# SoilMoistureSensorv2.net
KiCad netlist of a schematic drawn in Altium Designer
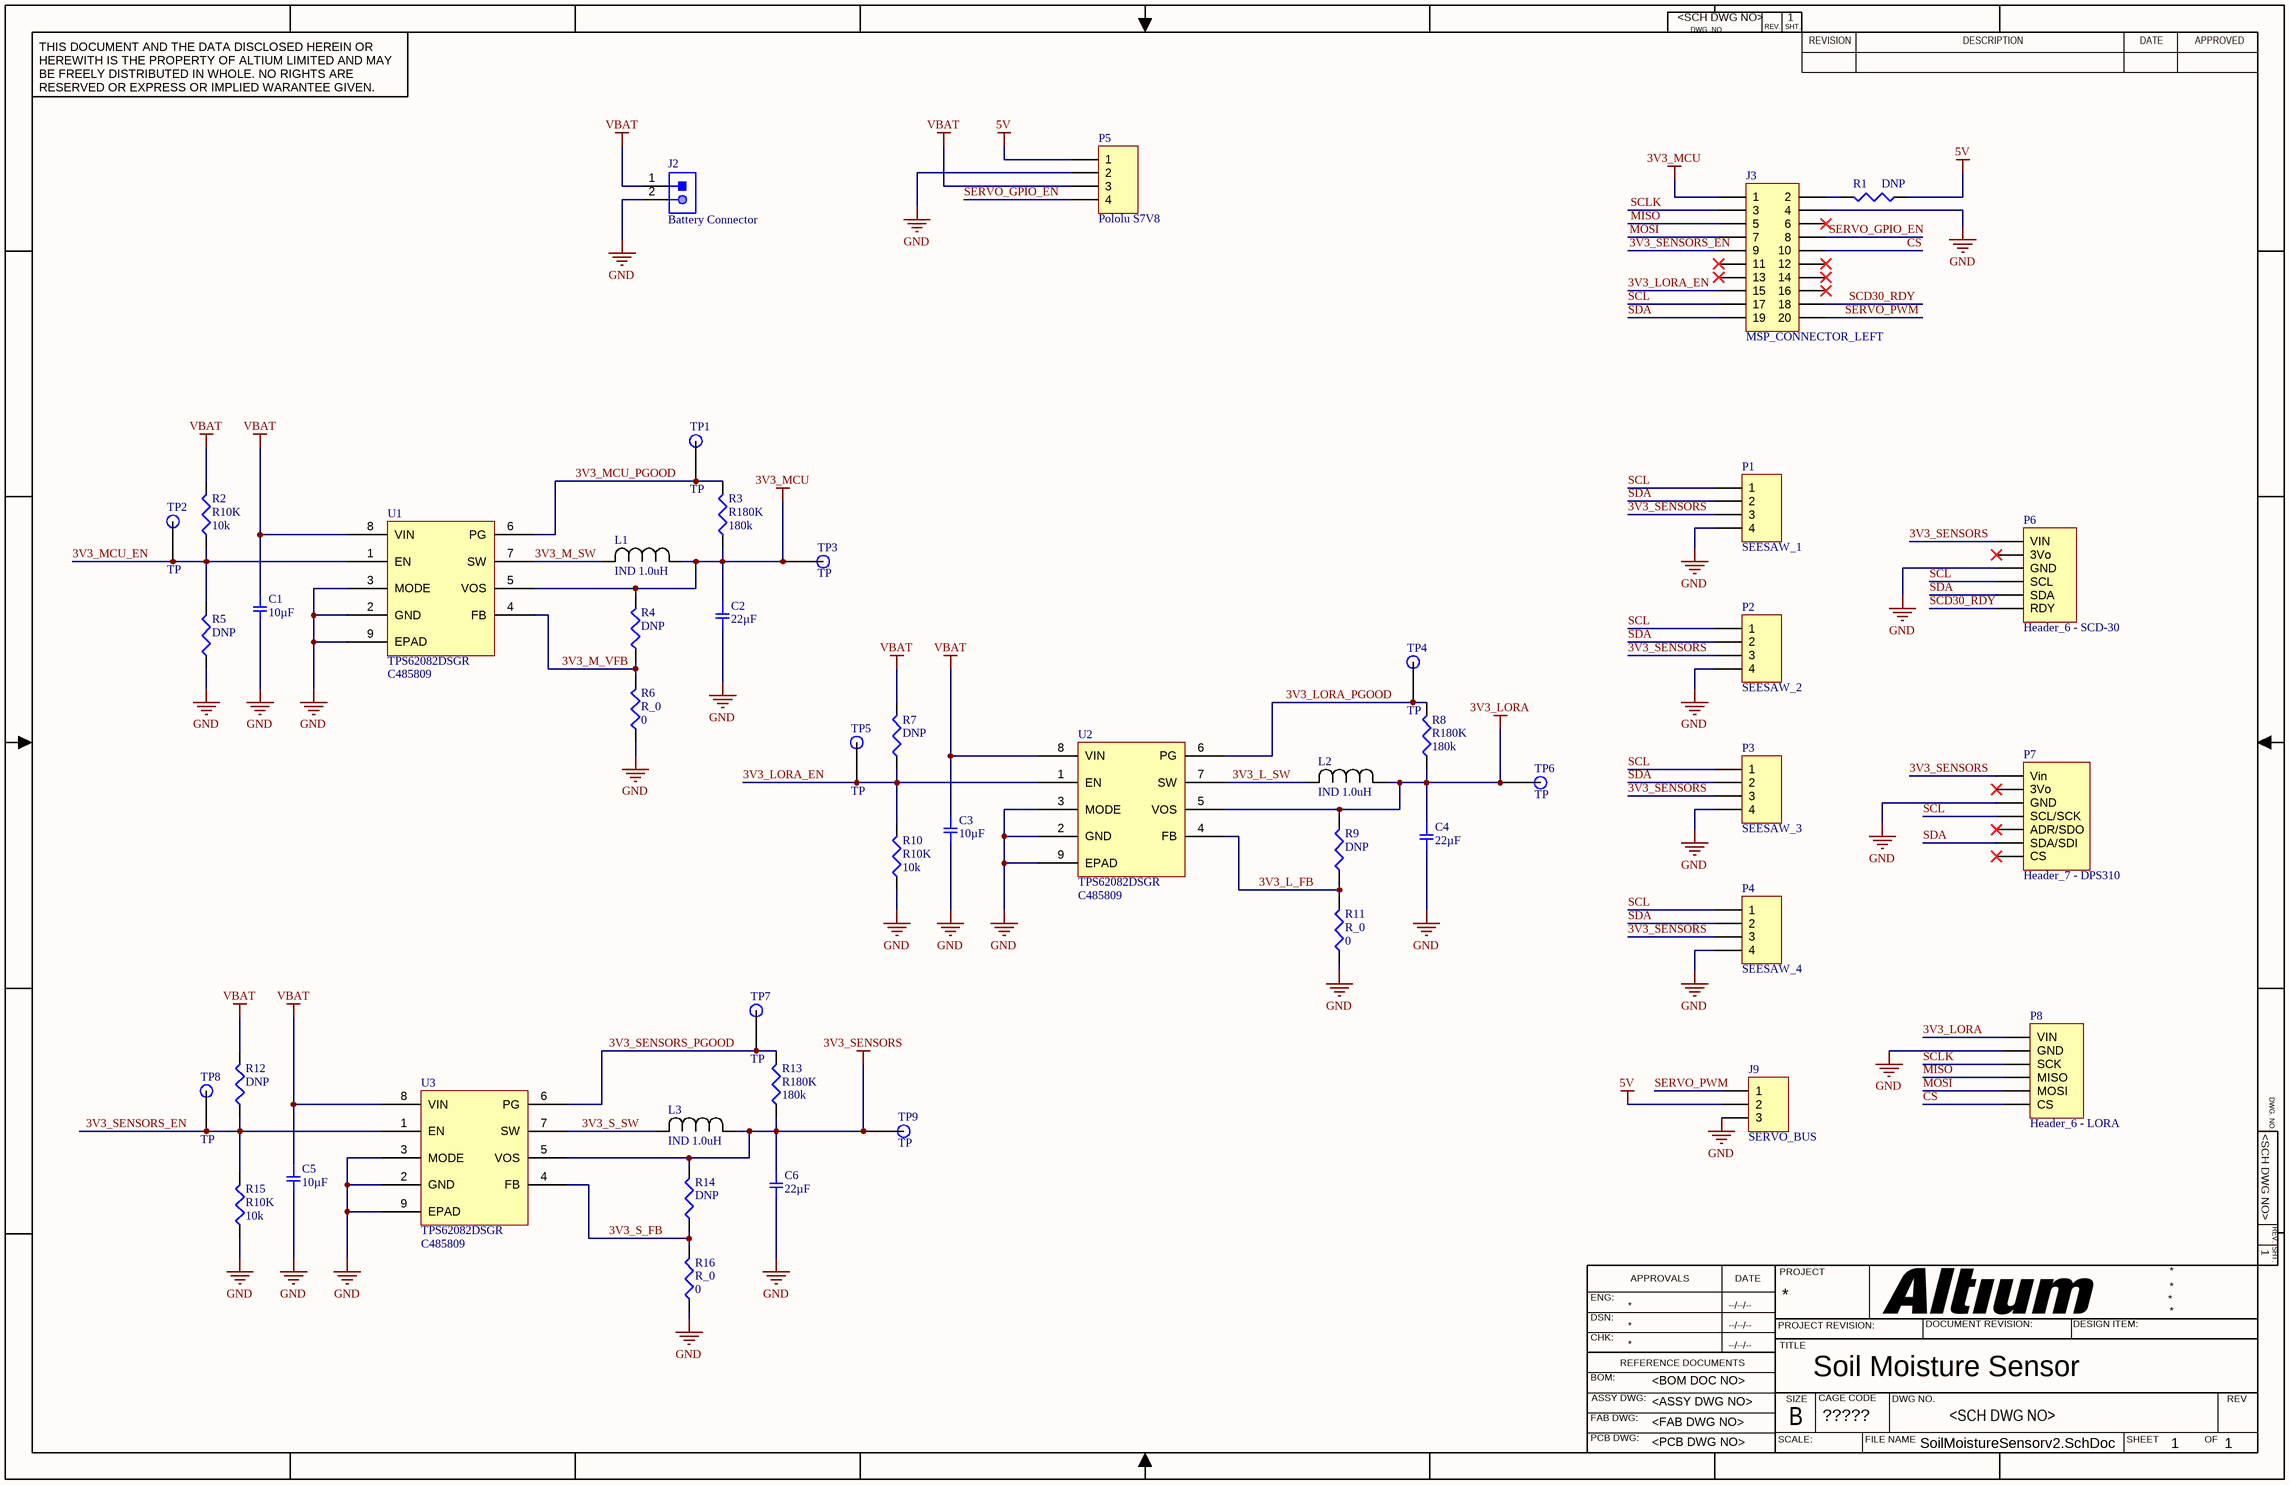
[diagram p0: SoilMoistureSensorv2.SchDoc]

(export (version "E")
  (design (tool "Eeschema 10.0.6"))
  (components
    (comp (ref "C1")
      (value "10µF")
      (footprint "SMD-0805C")
      (description "CAP CER 10UF 10V X7R 0805")
      (fields
        (field (name "PART NUMBER") "GCJ21BR71A106KE01L")
        (field (name "MANUFACTURER") "Murata Electronics North America")
      )
      (libsource (lib "capacitor") (part "GCJ21BR71A106KE01L"))
    )
    (comp (ref "C2")
      (value "22µF")
      (footprint "SMD-0805C")
      (description "CAP CER 22UF 10V X5R 0805")
      (fields
        (field (name "PART NUMBER") "GRT21BR61A226ME13L")
        (field (name "MANUFACTURER") "Murata Electronics North America")
      )
      (libsource (lib "capacitor") (part "GRT21BR61A226ME13L"))
    )
    (comp (ref "C3")
      (value "10µF")
      (footprint "SMD-0805C")
      (description "CAP CER 10UF 10V X7R 0805")
      (fields
        (field (name "PART NUMBER") "GCJ21BR71A106KE01L")
        (field (name "MANUFACTURER") "Murata Electronics North America")
      )
      (libsource (lib "capacitor") (part "GCJ21BR71A106KE01L"))
    )
    (comp (ref "C4")
      (value "22µF")
      (footprint "SMD-0805C")
      (description "CAP CER 22UF 10V X5R 0805")
      (fields
        (field (name "PART NUMBER") "GRT21BR61A226ME13L")
        (field (name "MANUFACTURER") "Murata Electronics North America")
      )
      (libsource (lib "capacitor") (part "GRT21BR61A226ME13L"))
    )
    (comp (ref "C5")
      (value "10µF")
      (footprint "SMD-0805C")
      (description "CAP CER 10UF 10V X7R 0805")
      (fields
        (field (name "PART NUMBER") "GCJ21BR71A106KE01L")
        (field (name "MANUFACTURER") "Murata Electronics North America")
      )
      (libsource (lib "capacitor") (part "GCJ21BR71A106KE01L"))
    )
    (comp (ref "C6")
      (value "22µF")
      (footprint "SMD-0805C")
      (description "CAP CER 22UF 10V X5R 0805")
      (fields
        (field (name "PART NUMBER") "GRT21BR61A226ME13L")
        (field (name "MANUFACTURER") "Murata Electronics North America")
      )
      (libsource (lib "capacitor") (part "GRT21BR61A226ME13L"))
    )
    (comp (ref "J2")
      (value "Battery Connector")
      (footprint "JST-S2B-PH-K-S_V")
      (fields (field (name "MANUFACTURER") "Japan Solderless Terminals"))
      (libsource (lib "University of Wisconsin-Madison CAE") (part "CN-1P-M-R2"))
    )
    (comp (ref "J3")
      (value "MSP_CONNECTOR_LEFT")
      (footprint "HDR2X10")
      (description "Header, 10-Pin, Dual row")
      (fields (field (name "PUBLISHER") "Altium Limited"))
      (libsource (lib "Miscellaneous Connectors") (part "Header 10X2"))
    )
    (comp (ref "J9")
      (value "SERVO_BUS")
      (footprint "HDR1X3")
      (description "Header, 3-Pin")
      (fields (field (name "PUBLISHER") "Altium Limited"))
      (libsource (lib "Miscellaneous Connectors") (part "Header 3"))
    )
    (comp (ref "L1")
      (value "IND 1.0uH")
      (footprint "INDP4340X15N")
      (description "SLO0415S1R0MTT")
      (fields (field (name "MANUFACTURER_PART_NUMBER") "XFL5030-102ME") (field (name "TOLERANCE") "+-20%"))
      (libsource (lib "SoilSensor") (part "IND 1.0uH"))
    )
    (comp (ref "L2")
      (value "IND 1.0uH")
      (footprint "INDP4340X15N")
      (description "SLO0415S1R0MTT")
      (fields (field (name "MANUFACTURER_PART_NUMBER") "XFL5030-102ME") (field (name "TOLERANCE") "+-20%"))
      (libsource (lib "SoilSensor") (part "IND 1.0uH"))
    )
    (comp (ref "L3")
      (value "IND 1.0uH")
      (footprint "INDP4340X15N")
      (description "SLO0415S1R0MTT")
      (fields (field (name "MANUFACTURER_PART_NUMBER") "XFL5030-102ME") (field (name "TOLERANCE") "+-20%"))
      (libsource (lib "SoilSensor") (part "IND 1.0uH"))
    )
    (comp (ref "P1")
      (value "SEESAW_1")
      (footprint "Pin Header 1x4 TH Pitch 2.54mm")
      (description "Header, 4-Pin")
      (fields (field (name "PUBLISHER") "Altium Limited"))
      (libsource (lib "SoilSensor") (part "Header 4"))
    )
    (comp (ref "P2")
      (value "SEESAW_2")
      (footprint "Pin Header 1x4 TH Pitch 2.54mm")
      (description "Header, 4-Pin")
      (fields (field (name "PUBLISHER") "Altium Limited"))
      (libsource (lib "SoilSensor") (part "Header 4"))
    )
    (comp (ref "P3")
      (value "SEESAW_3")
      (footprint "Pin Header 1x4 TH Pitch 2.54mm")
      (description "Header, 4-Pin")
      (fields (field (name "PUBLISHER") "Altium Limited"))
      (libsource (lib "SoilSensor") (part "Header 4"))
    )
    (comp (ref "P4")
      (value "SEESAW_4")
      (footprint "Pin Header 1x4 TH Pitch 2.54mm")
      (description "Header, 4-Pin")
      (fields (field (name "PUBLISHER") "Altium Limited"))
      (libsource (lib "SoilSensor") (part "Header 4"))
    )
    (comp (ref "P5")
      (value "Pololu S7V8")
      (footprint "Pin Header S7V8")
      (description "Header, 4-Pin")
      (fields (field (name "PUBLISHER") "Altium Limited"))
      (libsource (lib "SoilSensor") (part "Pololu S7V8"))
    )
    (comp (ref "P6")
      (value "Header_6 - SCD-30")
      (footprint "Pin Header SCD-30")
      (description "Header, 6-Pin")
      (fields (field (name "PUBLISHER") "Altium Limited"))
      (libsource (lib "SoilSensor") (part "Header_6 - SCD-30"))
    )
    (comp (ref "P7")
      (value "Header_7 - DPS310")
      (footprint "Pin Header DPS310")
      (description "Header, 7-Pin")
      (fields (field (name "PUBLISHER") "Altium Limited"))
      (libsource (lib "SoilSensor") (part "Header_7 - DPS310"))
    )
    (comp (ref "P8")
      (value "Header_6 - LORA")
      (footprint "Pin Header LORA")
      (description "Header, 6-Pin")
      (fields (field (name "PUBLISHER") "Altium Limited"))
      (libsource (lib "SoilSensor") (part "Header_6 - LORA"))
    )
    (comp (ref "R1")
      (value "DNP")
      (footprint "J1-0603")
      (description "Resistor")
      (fields (field (name "PUBLISHER") "Altium Limited"))
      (libsource (lib "Miscellaneous Devices") (part "Res3"))
    )
    (comp (ref "R2")
      (value "R10K")
      (footprint "J1-0603")
      (description "Resistor")
      (fields
        (field (name "ALTIUM_VALUE") "10k")
        (field (name "LCSC PART #") "C25804")
        (field (name "PUBLISHER") "Altium Limited")
      )
      (libsource (lib "Miscellaneous Devices") (part "Res3"))
    )
    (comp (ref "R3")
      (value "R180K")
      (footprint "J1-0603")
      (description "Resistor")
      (fields
        (field (name "ALTIUM_VALUE") "180k")
        (field (name "LCSC PART #") "C22827")
        (field (name "PUBLISHER") "Altium Limited")
      )
      (libsource (lib "Miscellaneous Devices") (part "Res3"))
    )
    (comp (ref "R4")
      (value "DNP")
      (footprint "J1-0603")
      (description "Resistor")
      (fields (field (name "PUBLISHER") "Altium Limited"))
      (libsource (lib "Miscellaneous Devices") (part "Res3"))
    )
    (comp (ref "R5")
      (value "DNP")
      (footprint "J1-0603")
      (description "Resistor")
      (fields (field (name "PUBLISHER") "Altium Limited"))
      (libsource (lib "Miscellaneous Devices") (part "Res3"))
    )
    (comp (ref "R6")
      (value "R_0")
      (footprint "J1-0603")
      (description "Resistor")
      (fields
        (field (name "ALTIUM_VALUE") "0")
        (field (name "LCSC PART #") "C21189")
        (field (name "PUBLISHER") "Altium Limited")
      )
      (libsource (lib "Miscellaneous Devices") (part "Res3"))
    )
    (comp (ref "R7")
      (value "DNP")
      (footprint "J1-0603")
      (description "Resistor")
      (fields (field (name "PUBLISHER") "Altium Limited"))
      (libsource (lib "Miscellaneous Devices") (part "Res3"))
    )
    (comp (ref "R8")
      (value "R180K")
      (footprint "J1-0603")
      (description "Resistor")
      (fields
        (field (name "ALTIUM_VALUE") "180k")
        (field (name "LCSC PART #") "C22827")
        (field (name "PUBLISHER") "Altium Limited")
      )
      (libsource (lib "Miscellaneous Devices") (part "Res3"))
    )
    (comp (ref "R9")
      (value "DNP")
      (footprint "J1-0603")
      (description "Resistor")
      (fields (field (name "PUBLISHER") "Altium Limited"))
      (libsource (lib "Miscellaneous Devices") (part "Res3"))
    )
    (comp (ref "R10")
      (value "R10K")
      (footprint "J1-0603")
      (description "Resistor")
      (fields
        (field (name "ALTIUM_VALUE") "10k")
        (field (name "LCSC PART #") "C25804")
        (field (name "PUBLISHER") "Altium Limited")
      )
      (libsource (lib "Miscellaneous Devices") (part "Res3"))
    )
    (comp (ref "R11")
      (value "R_0")
      (footprint "J1-0603")
      (description "Resistor")
      (fields
        (field (name "ALTIUM_VALUE") "0")
        (field (name "LCSC PART #") "C21189")
        (field (name "PUBLISHER") "Altium Limited")
      )
      (libsource (lib "Miscellaneous Devices") (part "Res3"))
    )
    (comp (ref "R12")
      (value "DNP")
      (footprint "J1-0603")
      (description "Resistor")
      (fields (field (name "PUBLISHER") "Altium Limited"))
      (libsource (lib "Miscellaneous Devices") (part "Res3"))
    )
    (comp (ref "R13")
      (value "R180K")
      (footprint "J1-0603")
      (description "Resistor")
      (fields
        (field (name "ALTIUM_VALUE") "180k")
        (field (name "LCSC PART #") "C22827")
        (field (name "PUBLISHER") "Altium Limited")
      )
      (libsource (lib "Miscellaneous Devices") (part "Res3"))
    )
    (comp (ref "R14")
      (value "DNP")
      (footprint "J1-0603")
      (description "Resistor")
      (fields (field (name "PUBLISHER") "Altium Limited"))
      (libsource (lib "Miscellaneous Devices") (part "Res3"))
    )
    (comp (ref "R15")
      (value "R10K")
      (footprint "J1-0603")
      (description "Resistor")
      (fields
        (field (name "ALTIUM_VALUE") "10k")
        (field (name "LCSC PART #") "C25804")
        (field (name "PUBLISHER") "Altium Limited")
      )
      (libsource (lib "Miscellaneous Devices") (part "Res3"))
    )
    (comp (ref "R16")
      (value "R_0")
      (footprint "J1-0603")
      (description "Resistor")
      (fields
        (field (name "ALTIUM_VALUE") "0")
        (field (name "LCSC PART #") "C21189")
        (field (name "PUBLISHER") "Altium Limited")
      )
      (libsource (lib "Miscellaneous Devices") (part "Res3"))
    )
    (comp (ref "TP1")
      (value "TP")
      (footprint "Test Point")
      (description "SMD TEST POINT")
      (libsource (lib "SoilSensor") (part "TP"))
    )
    (comp (ref "TP2")
      (value "TP")
      (footprint "Test Point")
      (description "SMD TEST POINT")
      (libsource (lib "SoilSensor") (part "TP"))
    )
    (comp (ref "TP3")
      (value "TP")
      (footprint "Test Point")
      (description "SMD TEST POINT")
      (libsource (lib "SoilSensor") (part "TP"))
    )
    (comp (ref "TP4")
      (value "TP")
      (footprint "Test Point")
      (description "SMD TEST POINT")
      (libsource (lib "SoilSensor") (part "TP"))
    )
    (comp (ref "TP5")
      (value "TP")
      (footprint "Test Point")
      (description "SMD TEST POINT")
      (libsource (lib "SoilSensor") (part "TP"))
    )
    (comp (ref "TP6")
      (value "TP")
      (footprint "Test Point")
      (description "SMD TEST POINT")
      (libsource (lib "SoilSensor") (part "TP"))
    )
    (comp (ref "TP7")
      (value "TP")
      (footprint "Test Point")
      (description "SMD TEST POINT")
      (libsource (lib "SoilSensor") (part "TP"))
    )
    (comp (ref "TP8")
      (value "TP")
      (footprint "Test Point")
      (description "SMD TEST POINT")
      (libsource (lib "SoilSensor") (part "TP"))
    )
    (comp (ref "TP9")
      (value "TP")
      (footprint "Test Point")
      (description "SMD TEST POINT")
      (libsource (lib "SoilSensor") (part "TP"))
    )
    (comp (ref "U1")
      (value "TPS62082DSGR")
      (footprint "DSG8_1P6X0P9")
      (fields (field (name "LCSC PART #") "C485809"))
      (libsource (lib "SoilSensor") (part "TPS62082DSGR"))
    )
    (comp (ref "U2")
      (value "TPS62082DSGR")
      (footprint "DSG8_1P6X0P9")
      (fields (field (name "LCSC PART #") "C485809"))
      (libsource (lib "SoilSensor") (part "TPS62082DSGR"))
    )
    (comp (ref "U3")
      (value "TPS62082DSGR")
      (footprint "DSG8_1P6X0P9")
      (fields (field (name "LCSC PART #") "C485809"))
      (libsource (lib "SoilSensor") (part "TPS62082DSGR"))
    )
  )
  (nets
    (net (code "1") (name "/3V3_LORA_EN") (class "Default")
      (node (ref "J3") (pin "15") (pinfunction "15_15") (pintype "passive"))
      (node (ref "R10") (pin "2") (pinfunction "2_2") (pintype "passive"))
      (node (ref "R7") (pin "1") (pinfunction "1_1") (pintype "passive"))
      (node (ref "TP5") (pin "1") (pinfunction "1_1") (pintype "passive"))
      (node (ref "U2") (pin "1") (pinfunction "EN_1") (pintype "power_in"))
    )
    (net (code "2") (name "/3V3_LORA_PGOOD") (class "Default")
      (node (ref "R8") (pin "2") (pinfunction "2_2") (pintype "passive"))
      (node (ref "TP4") (pin "1") (pinfunction "1_1") (pintype "passive"))
      (node (ref "U2") (pin "6") (pinfunction "PG_6") (pintype "power_in"))
    )
    (net (code "3") (name "/3V3_L_FB") (class "Default")
      (node (ref "R11") (pin "2") (pinfunction "2_2") (pintype "passive"))
      (node (ref "R9") (pin "1") (pinfunction "1_1") (pintype "passive"))
      (node (ref "U2") (pin "4") (pinfunction "FB_4") (pintype "power_in"))
    )
    (net (code "4") (name "/3V3_L_SW") (class "Default")
      (node (ref "L2") (pin "2") (pinfunction "2_2") (pintype "passive"))
      (node (ref "U2") (pin "7") (pinfunction "SW_7") (pintype "power_in"))
    )
    (net (code "5") (name "/3V3_MCU_EN") (class "Default")
      (node (ref "R2") (pin "1") (pinfunction "1_1") (pintype "passive"))
      (node (ref "R5") (pin "2") (pinfunction "2_2") (pintype "passive"))
      (node (ref "TP2") (pin "1") (pinfunction "1_1") (pintype "passive"))
      (node (ref "U1") (pin "1") (pinfunction "EN_1") (pintype "power_in"))
    )
    (net (code "6") (name "/3V3_MCU_PGOOD") (class "Default")
      (node (ref "R3") (pin "2") (pinfunction "2_2") (pintype "passive"))
      (node (ref "TP1") (pin "1") (pinfunction "1_1") (pintype "passive"))
      (node (ref "U1") (pin "6") (pinfunction "PG_6") (pintype "power_in"))
    )
    (net (code "7") (name "/3V3_M_SW") (class "Default")
      (node (ref "L1") (pin "2") (pinfunction "2_2") (pintype "passive"))
      (node (ref "U1") (pin "7") (pinfunction "SW_7") (pintype "power_in"))
    )
    (net (code "8") (name "/3V3_M_VFB") (class "Default")
      (node (ref "R4") (pin "1") (pinfunction "1_1") (pintype "passive"))
      (node (ref "R6") (pin "2") (pinfunction "2_2") (pintype "passive"))
      (node (ref "U1") (pin "4") (pinfunction "FB_4") (pintype "power_in"))
    )
    (net (code "9") (name "/3V3_SENSORS_EN") (class "Default")
      (node (ref "J3") (pin "9") (pinfunction "9_9") (pintype "passive"))
      (node (ref "R12") (pin "1") (pinfunction "1_1") (pintype "passive"))
      (node (ref "R15") (pin "2") (pinfunction "2_2") (pintype "passive"))
      (node (ref "TP8") (pin "1") (pinfunction "1_1") (pintype "passive"))
      (node (ref "U3") (pin "1") (pinfunction "EN_1") (pintype "power_in"))
    )
    (net (code "10") (name "/3V3_SENSORS_PGOOD") (class "Default")
      (node (ref "R13") (pin "2") (pinfunction "2_2") (pintype "passive"))
      (node (ref "TP7") (pin "1") (pinfunction "1_1") (pintype "passive"))
      (node (ref "U3") (pin "6") (pinfunction "PG_6") (pintype "power_in"))
    )
    (net (code "11") (name "/3V3_S_FB") (class "Default")
      (node (ref "R14") (pin "1") (pinfunction "1_1") (pintype "passive"))
      (node (ref "R16") (pin "2") (pinfunction "2_2") (pintype "passive"))
      (node (ref "U3") (pin "4") (pinfunction "FB_4") (pintype "power_in"))
    )
    (net (code "12") (name "/3V3_S_SW") (class "Default")
      (node (ref "L3") (pin "2") (pinfunction "2_2") (pintype "passive"))
      (node (ref "U3") (pin "7") (pinfunction "SW_7") (pintype "power_in"))
    )
    (net (code "13") (name "/CS") (class "Default")
      (node (ref "J3") (pin "10") (pinfunction "10_10") (pintype "passive"))
      (node (ref "P8") (pin "6") (pinfunction "CS_6") (pintype "passive"))
    )
    (net (code "14") (name "/MISO") (class "Default")
      (node (ref "J3") (pin "5") (pinfunction "5_5") (pintype "passive"))
      (node (ref "P8") (pin "4") (pinfunction "MISO_4") (pintype "passive"))
    )
    (net (code "15") (name "/MOSI") (class "Default")
      (node (ref "J3") (pin "7") (pinfunction "7_7") (pintype "passive"))
      (node (ref "P8") (pin "5") (pinfunction "MOSI_5") (pintype "passive"))
    )
    (net (code "16") (name "/SCD30_RDY") (class "Default")
      (node (ref "J3") (pin "18") (pinfunction "18_18") (pintype "passive"))
      (node (ref "P6") (pin "6") (pinfunction "RDY_6") (pintype "passive"))
    )
    (net (code "17") (name "/SCL") (class "Default")
      (node (ref "J3") (pin "17") (pinfunction "17_17") (pintype "passive"))
      (node (ref "P1") (pin "1") (pinfunction "1_1") (pintype "passive"))
      (node (ref "P2") (pin "1") (pinfunction "1_1") (pintype "passive"))
      (node (ref "P3") (pin "1") (pinfunction "1_1") (pintype "passive"))
      (node (ref "P4") (pin "1") (pinfunction "1_1") (pintype "passive"))
      (node (ref "P6") (pin "4") (pinfunction "SCL_4") (pintype "passive"))
      (node (ref "P7") (pin "4") (pinfunction "SCL/SCK_4") (pintype "passive"))
    )
    (net (code "18") (name "/SCLK") (class "Default")
      (node (ref "J3") (pin "3") (pinfunction "3_3") (pintype "passive"))
      (node (ref "P8") (pin "3") (pinfunction "SCK_3") (pintype "passive"))
    )
    (net (code "19") (name "/SDA") (class "Default")
      (node (ref "J3") (pin "19") (pinfunction "19_19") (pintype "passive"))
      (node (ref "P1") (pin "2") (pinfunction "2_2") (pintype "passive"))
      (node (ref "P2") (pin "2") (pinfunction "2_2") (pintype "passive"))
      (node (ref "P3") (pin "2") (pinfunction "2_2") (pintype "passive"))
      (node (ref "P4") (pin "2") (pinfunction "2_2") (pintype "passive"))
      (node (ref "P6") (pin "5") (pinfunction "SDA_5") (pintype "passive"))
      (node (ref "P7") (pin "6") (pinfunction "SDA/SDI_6") (pintype "passive"))
    )
    (net (code "20") (name "/SERVO_GPIO_EN") (class "Default")
      (node (ref "J3") (pin "8") (pinfunction "8_8") (pintype "passive"))
      (node (ref "P5") (pin "4") (pinfunction "4_4") (pintype "passive"))
    )
    (net (code "21") (name "/SERVO_PWM") (class "Default")
      (node (ref "J3") (pin "20") (pinfunction "20_20") (pintype "passive"))
      (node (ref "J9") (pin "1") (pinfunction "1_1") (pintype "passive"))
    )
    (net (code "22") (name "3V3_LORA") (class "Default")
      (node (ref "C4") (pin "1") (pinfunction "1_1") (pintype "passive"))
      (node (ref "L2") (pin "1") (pinfunction "1_1") (pintype "passive"))
      (node (ref "P8") (pin "1") (pinfunction "VIN_1") (pintype "passive"))
      (node (ref "R8") (pin "1") (pinfunction "1_1") (pintype "passive"))
      (node (ref "R9") (pin "2") (pinfunction "2_2") (pintype "passive"))
      (node (ref "TP6") (pin "1") (pinfunction "1_1") (pintype "passive"))
      (node (ref "U2") (pin "5") (pinfunction "VOS_5") (pintype "power_in"))
    )
    (net (code "23") (name "3V3_MCU") (class "Default")
      (node (ref "C2") (pin "1") (pinfunction "1_1") (pintype "passive"))
      (node (ref "J3") (pin "1") (pinfunction "1_1") (pintype "passive"))
      (node (ref "L1") (pin "1") (pinfunction "1_1") (pintype "passive"))
      (node (ref "R3") (pin "1") (pinfunction "1_1") (pintype "passive"))
      (node (ref "R4") (pin "2") (pinfunction "2_2") (pintype "passive"))
      (node (ref "TP3") (pin "1") (pinfunction "1_1") (pintype "passive"))
      (node (ref "U1") (pin "5") (pinfunction "VOS_5") (pintype "power_in"))
    )
    (net (code "24") (name "3V3_SENSORS") (class "Default")
      (node (ref "C6") (pin "1") (pinfunction "1_1") (pintype "passive"))
      (node (ref "L3") (pin "1") (pinfunction "1_1") (pintype "passive"))
      (node (ref "P1") (pin "3") (pinfunction "3_3") (pintype "passive"))
      (node (ref "P2") (pin "3") (pinfunction "3_3") (pintype "passive"))
      (node (ref "P3") (pin "3") (pinfunction "3_3") (pintype "passive"))
      (node (ref "P4") (pin "3") (pinfunction "3_3") (pintype "passive"))
      (node (ref "P6") (pin "1") (pinfunction "VIN_1") (pintype "passive"))
      (node (ref "P7") (pin "1") (pinfunction "Vin_1") (pintype "passive"))
      (node (ref "R13") (pin "1") (pinfunction "1_1") (pintype "passive"))
      (node (ref "R14") (pin "2") (pinfunction "2_2") (pintype "passive"))
      (node (ref "TP9") (pin "1") (pinfunction "1_1") (pintype "passive"))
      (node (ref "U3") (pin "5") (pinfunction "VOS_5") (pintype "power_in"))
    )
    (net (code "25") (name "5V") (class "Default")
      (node (ref "J9") (pin "2") (pinfunction "2_2") (pintype "passive"))
      (node (ref "P5") (pin "1") (pinfunction "1_1") (pintype "passive"))
      (node (ref "R1") (pin "1") (pinfunction "1_1") (pintype "passive"))
    )
    (net (code "26") (name "GND") (class "Default")
      (node (ref "C1") (pin "2") (pinfunction "2_2") (pintype "passive"))
      (node (ref "C2") (pin "2") (pinfunction "2_2") (pintype "passive"))
      (node (ref "C3") (pin "2") (pinfunction "2_2") (pintype "passive"))
      (node (ref "C4") (pin "2") (pinfunction "2_2") (pintype "passive"))
      (node (ref "C5") (pin "2") (pinfunction "2_2") (pintype "passive"))
      (node (ref "C6") (pin "2") (pinfunction "2_2") (pintype "passive"))
      (node (ref "J2") (pin "2") (pinfunction "2_2") (pintype "passive"))
      (node (ref "J3") (pin "4") (pinfunction "4_4") (pintype "passive"))
      (node (ref "J9") (pin "3") (pinfunction "3_3") (pintype "passive"))
      (node (ref "P1") (pin "4") (pinfunction "4_4") (pintype "passive"))
      (node (ref "P2") (pin "4") (pinfunction "4_4") (pintype "passive"))
      (node (ref "P3") (pin "4") (pinfunction "4_4") (pintype "passive"))
      (node (ref "P4") (pin "4") (pinfunction "4_4") (pintype "passive"))
      (node (ref "P5") (pin "2") (pinfunction "2_2") (pintype "passive"))
      (node (ref "P6") (pin "3") (pinfunction "GND_3") (pintype "passive"))
      (node (ref "P7") (pin "3") (pinfunction "GND_3") (pintype "passive"))
      (node (ref "P8") (pin "2") (pinfunction "GND_2") (pintype "passive"))
      (node (ref "R10") (pin "1") (pinfunction "1_1") (pintype "passive"))
      (node (ref "R11") (pin "1") (pinfunction "1_1") (pintype "passive"))
      (node (ref "R15") (pin "1") (pinfunction "1_1") (pintype "passive"))
      (node (ref "R16") (pin "1") (pinfunction "1_1") (pintype "passive"))
      (node (ref "R5") (pin "1") (pinfunction "1_1") (pintype "passive"))
      (node (ref "R6") (pin "1") (pinfunction "1_1") (pintype "passive"))
      (node (ref "U1") (pin "2") (pinfunction "GND_2") (pintype "power_in"))
      (node (ref "U1") (pin "3") (pinfunction "MODE_3") (pintype "power_in"))
      (node (ref "U1") (pin "9") (pinfunction "EPAD_9") (pintype "power_in"))
      (node (ref "U2") (pin "2") (pinfunction "GND_2") (pintype "power_in"))
      (node (ref "U2") (pin "3") (pinfunction "MODE_3") (pintype "power_in"))
      (node (ref "U2") (pin "9") (pinfunction "EPAD_9") (pintype "power_in"))
      (node (ref "U3") (pin "2") (pinfunction "GND_2") (pintype "power_in"))
      (node (ref "U3") (pin "3") (pinfunction "MODE_3") (pintype "power_in"))
      (node (ref "U3") (pin "9") (pinfunction "EPAD_9") (pintype "power_in"))
    )
    (net (code "27") (name "Net-(J3-Pad2)") (class "Default")
      (node (ref "J3") (pin "2") (pinfunction "2_2") (pintype "passive"))
      (node (ref "R1") (pin "2") (pinfunction "2_2") (pintype "passive"))
    )
    (net (code "28") (name "VBAT") (class "Default")
      (node (ref "C1") (pin "1") (pinfunction "1_1") (pintype "passive"))
      (node (ref "C3") (pin "1") (pinfunction "1_1") (pintype "passive"))
      (node (ref "C5") (pin "1") (pinfunction "1_1") (pintype "passive"))
      (node (ref "J2") (pin "1") (pinfunction "1_1") (pintype "passive"))
      (node (ref "P5") (pin "3") (pinfunction "3_3") (pintype "passive"))
      (node (ref "R12") (pin "2") (pinfunction "2_2") (pintype "passive"))
      (node (ref "R2") (pin "2") (pinfunction "2_2") (pintype "passive"))
      (node (ref "R7") (pin "2") (pinfunction "2_2") (pintype "passive"))
      (node (ref "U1") (pin "8") (pinfunction "VIN_8") (pintype "power_in"))
      (node (ref "U2") (pin "8") (pinfunction "VIN_8") (pintype "power_in"))
      (node (ref "U3") (pin "8") (pinfunction "VIN_8") (pintype "power_in"))
    )
    (net (code "29") (name "unconnected-(J3-Pad6)") (class "Default")
      (node (ref "J3") (pin "6") (pinfunction "6_6") (pintype "passive+no_connect"))
    )
    (net (code "30") (name "unconnected-(J3-Pad11)") (class "Default")
      (node (ref "J3") (pin "11") (pinfunction "11_11") (pintype "passive+no_connect"))
    )
    (net (code "31") (name "unconnected-(J3-Pad12)") (class "Default")
      (node (ref "J3") (pin "12") (pinfunction "12_12") (pintype "passive+no_connect"))
    )
    (net (code "32") (name "unconnected-(J3-Pad13)") (class "Default")
      (node (ref "J3") (pin "13") (pinfunction "13_13") (pintype "passive+no_connect"))
    )
    (net (code "33") (name "unconnected-(J3-Pad14)") (class "Default")
      (node (ref "J3") (pin "14") (pinfunction "14_14") (pintype "passive+no_connect"))
    )
    (net (code "34") (name "unconnected-(J3-Pad16)") (class "Default")
      (node (ref "J3") (pin "16") (pinfunction "16_16") (pintype "passive+no_connect"))
    )
    (net (code "35") (name "unconnected-(P6-3Vo-Pad2)") (class "Default")
      (node (ref "P6") (pin "2") (pinfunction "3Vo_2") (pintype "passive+no_connect"))
    )
    (net (code "36") (name "unconnected-(P7-3Vo-Pad2)") (class "Default")
      (node (ref "P7") (pin "2") (pinfunction "3Vo_2") (pintype "passive+no_connect"))
    )
    (net (code "37") (name "unconnected-(P7-ADR{slash}SDO-Pad5)") (class "Default")
      (node (ref "P7") (pin "5") (pinfunction "ADR/SDO_5") (pintype "passive+no_connect"))
    )
    (net (code "38") (name "unconnected-(P7-CS-Pad7)") (class "Default")
      (node (ref "P7") (pin "7") (pinfunction "CS_7") (pintype "passive+no_connect"))
    )
  )
)
